# Audio_panel_Embedded_Mega_breakout.net
KiCad netlist of a schematic drawn in EAGLE
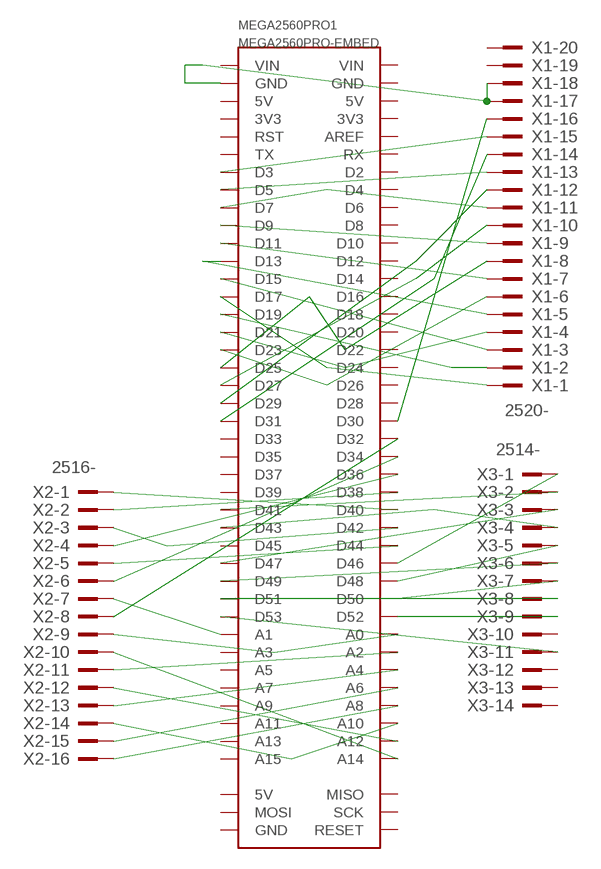
[diagram p0: schematic, sheet 1]

(export (version "E")
  (design (tool "Eeschema 10.0.6"))
  (components
    (comp (ref "MEGA2560PRO1")
      (value "MEGA2560PRO-EMBED")
      (footprint "eagle-import:MEGA2560PRO-EMBED")
      (libsource (lib "eagle-import") (part "MEGA2560PRO-EMBED"))
    )
    (comp (ref "X1")
      (value "2520-")
      (footprint "eagle-import:PAK100_2500-20")
      (libsource (lib "eagle-import") (part "2520-"))
    )
    (comp (ref "X2")
      (value "2516-")
      (footprint "eagle-import:PAK100_2500-16")
      (libsource (lib "eagle-import") (part "2516-"))
    )
    (comp (ref "X3")
      (value "2514-")
      (footprint "eagle-import:PAK100_2500-14")
      (libsource (lib "eagle-import") (part "2514-"))
    )
  )
  (nets
    (net (code "1") (name "Net-(X1A-KL)") (class "Default")
      (node (ref "MEGA2560PRO1") (pin "D17") (pinfunction "D17_D17") (pintype "bidirectional"))
      (node (ref "X1") (pin "1") (pinfunction "KL_1") (pintype "passive"))
    )
    (net (code "2") (name "Net-(X1B-KL)") (class "Default")
      (node (ref "MEGA2560PRO1") (pin "D27") (pinfunction "D27_D27") (pintype "bidirectional"))
      (node (ref "X1") (pin "10") (pinfunction "KL_10") (pintype "passive"))
    )
    (net (code "3") (name "Net-(X1C-KL)") (class "Default")
      (node (ref "MEGA2560PRO1") (pin "D7") (pinfunction "D7_D7") (pintype "bidirectional"))
      (node (ref "X1") (pin "11") (pinfunction "KL_11") (pintype "passive"))
    )
    (net (code "4") (name "Net-(X1D-KL)") (class "Default")
      (node (ref "MEGA2560PRO1") (pin "D29") (pinfunction "D29_D29") (pintype "bidirectional"))
      (node (ref "X1") (pin "12") (pinfunction "KL_12") (pintype "passive"))
    )
    (net (code "5") (name "Net-(X1E-KL)") (class "Default")
      (node (ref "MEGA2560PRO1") (pin "D5") (pinfunction "D5_D5") (pintype "bidirectional"))
      (node (ref "X1") (pin "13") (pinfunction "KL_13") (pintype "passive"))
    )
    (net (code "6") (name "Net-(X1F-KL)") (class "Default")
      (node (ref "MEGA2560PRO1") (pin "D31") (pinfunction "D31_D31") (pintype "bidirectional"))
      (node (ref "X1") (pin "14") (pinfunction "KL_14") (pintype "passive"))
    )
    (net (code "7") (name "Net-(X1G-KL)") (class "Default")
      (node (ref "MEGA2560PRO1") (pin "D3") (pinfunction "D3_D3") (pintype "bidirectional"))
      (node (ref "X1") (pin "15") (pinfunction "KL_15") (pintype "passive"))
    )
    (net (code "8") (name "Net-(X1H-KL)") (class "Default")
      (node (ref "MEGA2560PRO1") (pin "D30") (pinfunction "D30_D30") (pintype "bidirectional"))
      (node (ref "X1") (pin "16") (pinfunction "KL_16") (pintype "passive"))
    )
    (net (code "9") (name "Net-(X1I-KL)") (class "Default")
      (node (ref "MEGA2560PRO1") (pin "GND@1") (pinfunction "GND_GND@1") (pintype "bidirectional"))
      (node (ref "X1") (pin "17") (pinfunction "KL_17") (pintype "passive"))
      (node (ref "X1") (pin "18") (pinfunction "KL_18") (pintype "passive"))
    )
    (net (code "10") (name "Net-(X1L-KL)") (class "Default")
      (node (ref "MEGA2560PRO1") (pin "D19") (pinfunction "D19_D19") (pintype "bidirectional"))
      (node (ref "X1") (pin "2") (pinfunction "KL_2") (pintype "passive"))
    )
    (net (code "11") (name "Net-(X1N-KL)") (class "Default")
      (node (ref "MEGA2560PRO1") (pin "D15") (pinfunction "D15_D15") (pintype "bidirectional"))
      (node (ref "X1") (pin "3") (pinfunction "KL_3") (pintype "passive"))
    )
    (net (code "12") (name "Net-(X1O-KL)") (class "Default")
      (node (ref "MEGA2560PRO1") (pin "D21") (pinfunction "D21_D21") (pintype "bidirectional"))
      (node (ref "X1") (pin "4") (pinfunction "KL_4") (pintype "passive"))
    )
    (net (code "13") (name "Net-(X1P-KL)") (class "Default")
      (node (ref "MEGA2560PRO1") (pin "D13") (pinfunction "D13_D13") (pintype "bidirectional"))
      (node (ref "X1") (pin "5") (pinfunction "KL_5") (pintype "passive"))
    )
    (net (code "14") (name "Net-(X1Q-KL)") (class "Default")
      (node (ref "MEGA2560PRO1") (pin "D23") (pinfunction "D23_D23") (pintype "bidirectional"))
      (node (ref "X1") (pin "6") (pinfunction "KL_6") (pintype "passive"))
    )
    (net (code "15") (name "Net-(X1R-KL)") (class "Default")
      (node (ref "MEGA2560PRO1") (pin "D11") (pinfunction "D11_D11") (pintype "bidirectional"))
      (node (ref "X1") (pin "7") (pinfunction "KL_7") (pintype "passive"))
    )
    (net (code "16") (name "Net-(X1S-KL)") (class "Default")
      (node (ref "MEGA2560PRO1") (pin "D25") (pinfunction "D25_D25") (pintype "bidirectional"))
      (node (ref "X1") (pin "8") (pinfunction "KL_8") (pintype "passive"))
    )
    (net (code "17") (name "Net-(X1T-KL)") (class "Default")
      (node (ref "MEGA2560PRO1") (pin "D9") (pinfunction "D9_D9") (pintype "bidirectional"))
      (node (ref "X1") (pin "9") (pinfunction "KL_9") (pintype "passive"))
    )
    (net (code "18") (name "Net-(X2A-KL)") (class "Default")
      (node (ref "MEGA2560PRO1") (pin "D40") (pinfunction "D40_D40") (pintype "bidirectional"))
      (node (ref "X2") (pin "1") (pinfunction "KL_1") (pintype "passive"))
    )
    (net (code "19") (name "Net-(X2B-KL)") (class "Default")
      (node (ref "MEGA2560PRO1") (pin "A14") (pinfunction "A14_A14") (pintype "bidirectional"))
      (node (ref "X2") (pin "10") (pinfunction "KL_10") (pintype "passive"))
    )
    (net (code "20") (name "Net-(X2C-KL)") (class "Default")
      (node (ref "MEGA2560PRO1") (pin "A2") (pinfunction "A2_A2") (pintype "bidirectional"))
      (node (ref "X2") (pin "11") (pinfunction "KL_11") (pintype "passive"))
    )
    (net (code "21") (name "Net-(X2D-KL)") (class "Default")
      (node (ref "MEGA2560PRO1") (pin "A12") (pinfunction "A12_A12") (pintype "bidirectional"))
      (node (ref "X2") (pin "12") (pinfunction "KL_12") (pintype "passive"))
    )
    (net (code "22") (name "Net-(X2E-KL)") (class "Default")
      (node (ref "MEGA2560PRO1") (pin "A4") (pinfunction "A4_A4") (pintype "bidirectional"))
      (node (ref "X2") (pin "13") (pinfunction "KL_13") (pintype "passive"))
    )
    (net (code "23") (name "Net-(X2F-KL)") (class "Default")
      (node (ref "MEGA2560PRO1") (pin "A10") (pinfunction "A10_A10") (pintype "bidirectional"))
      (node (ref "X2") (pin "14") (pinfunction "KL_14") (pintype "passive"))
    )
    (net (code "24") (name "Net-(X2G-KL)") (class "Default")
      (node (ref "MEGA2560PRO1") (pin "A6") (pinfunction "A6_A6") (pintype "bidirectional"))
      (node (ref "X2") (pin "15") (pinfunction "KL_15") (pintype "passive"))
    )
    (net (code "25") (name "Net-(X2H-KL)") (class "Default")
      (node (ref "MEGA2560PRO1") (pin "A8") (pinfunction "A8_A8") (pintype "bidirectional"))
      (node (ref "X2") (pin "16") (pinfunction "KL_16") (pintype "passive"))
    )
    (net (code "26") (name "Net-(X2I-KL)") (class "Default")
      (node (ref "MEGA2560PRO1") (pin "D38") (pinfunction "D38_D38") (pintype "bidirectional"))
      (node (ref "X2") (pin "2") (pinfunction "KL_2") (pintype "passive"))
    )
    (net (code "27") (name "Net-(X2J-KL)") (class "Default")
      (node (ref "MEGA2560PRO1") (pin "D42") (pinfunction "D42_D42") (pintype "bidirectional"))
      (node (ref "X2") (pin "3") (pinfunction "KL_3") (pintype "passive"))
    )
    (net (code "28") (name "Net-(X2K-KL)") (class "Default")
      (node (ref "MEGA2560PRO1") (pin "D36") (pinfunction "D36_D36") (pintype "bidirectional"))
      (node (ref "X2") (pin "4") (pinfunction "KL_4") (pintype "passive"))
    )
    (net (code "29") (name "Net-(X2L-KL)") (class "Default")
      (node (ref "MEGA2560PRO1") (pin "D44") (pinfunction "D44_D44") (pintype "bidirectional"))
      (node (ref "X2") (pin "5") (pinfunction "KL_5") (pintype "passive"))
    )
    (net (code "30") (name "Net-(X2M-KL)") (class "Default")
      (node (ref "MEGA2560PRO1") (pin "D34") (pinfunction "D34_D34") (pintype "bidirectional"))
      (node (ref "X2") (pin "6") (pinfunction "KL_6") (pintype "passive"))
    )
    (net (code "31") (name "Net-(X2N-KL)") (class "Default")
      (node (ref "MEGA2560PRO1") (pin "A1") (pinfunction "A1_A1") (pintype "bidirectional"))
      (node (ref "X2") (pin "7") (pinfunction "KL_7") (pintype "passive"))
    )
    (net (code "32") (name "Net-(X2O-KL)") (class "Default")
      (node (ref "MEGA2560PRO1") (pin "D32") (pinfunction "D32_D32") (pintype "bidirectional"))
      (node (ref "X2") (pin "8") (pinfunction "KL_8") (pintype "passive"))
    )
    (net (code "33") (name "Net-(X2P-KL)") (class "Default")
      (node (ref "MEGA2560PRO1") (pin "A0") (pinfunction "A0_A0") (pintype "bidirectional"))
      (node (ref "X2") (pin "9") (pinfunction "KL_9") (pintype "passive"))
    )
    (net (code "34") (name "Net-(X3A-KL)") (class "Default")
      (node (ref "MEGA2560PRO1") (pin "D46") (pinfunction "D46_D46") (pintype "bidirectional"))
      (node (ref "X3") (pin "1") (pinfunction "KL_1") (pintype "passive"))
    )
    (net (code "35") (name "Net-(X3C-KL)") (class "Default")
      (node (ref "MEGA2560PRO1") (pin "D53") (pinfunction "D53_D53") (pintype "bidirectional"))
      (node (ref "X3") (pin "11") (pinfunction "KL_11") (pintype "passive"))
    )
    (net (code "36") (name "Net-(X3G-KL)") (class "Default")
      (node (ref "MEGA2560PRO1") (pin "D41") (pinfunction "D41_D41") (pintype "bidirectional"))
      (node (ref "X3") (pin "2") (pinfunction "KL_2") (pintype "passive"))
    )
    (net (code "37") (name "Net-(X3H-KL)") (class "Default")
      (node (ref "MEGA2560PRO1") (pin "D47") (pinfunction "D47_D47") (pintype "bidirectional"))
      (node (ref "X3") (pin "3") (pinfunction "KL_3") (pintype "passive"))
    )
    (net (code "38") (name "Net-(X3I-KL)") (class "Default")
      (node (ref "MEGA2560PRO1") (pin "D43") (pinfunction "D43_D43") (pintype "bidirectional"))
      (node (ref "X3") (pin "4") (pinfunction "KL_4") (pintype "passive"))
    )
    (net (code "39") (name "Net-(X3J-KL)") (class "Default")
      (node (ref "MEGA2560PRO1") (pin "D48") (pinfunction "D48_D48") (pintype "bidirectional"))
      (node (ref "X3") (pin "5") (pinfunction "KL_5") (pintype "passive"))
    )
    (net (code "40") (name "Net-(X3K-KL)") (class "Default")
      (node (ref "MEGA2560PRO1") (pin "D49") (pinfunction "D49_D49") (pintype "bidirectional"))
      (node (ref "X3") (pin "6") (pinfunction "KL_6") (pintype "passive"))
    )
    (net (code "41") (name "Net-(X3L-KL)") (class "Default")
      (node (ref "MEGA2560PRO1") (pin "D50") (pinfunction "D50_D50") (pintype "bidirectional"))
      (node (ref "X3") (pin "7") (pinfunction "KL_7") (pintype "passive"))
    )
    (net (code "42") (name "Net-(X3M-KL)") (class "Default")
      (node (ref "MEGA2560PRO1") (pin "D51") (pinfunction "D51_D51") (pintype "bidirectional"))
      (node (ref "X3") (pin "8") (pinfunction "KL_8") (pintype "passive"))
    )
    (net (code "43") (name "Net-(X3N-KL)") (class "Default")
      (node (ref "MEGA2560PRO1") (pin "D52") (pinfunction "D52_D52") (pintype "bidirectional"))
      (node (ref "X3") (pin "9") (pinfunction "KL_9") (pintype "passive"))
    )
    (net (code "44") (name "unconnected-(MEGA2560PRO1-3V3-Pad3V3@1)") (class "Default")
      (node (ref "MEGA2560PRO1") (pin "3V3@1") (pinfunction "3V3_3V3@1") (pintype "bidirectional"))
    )
    (net (code "45") (name "unconnected-(MEGA2560PRO1-3V3-Pad3V3@2)") (class "Default")
      (node (ref "MEGA2560PRO1") (pin "3V3@2") (pinfunction "3V3_3V3@2") (pintype "bidirectional"))
    )
    (net (code "46") (name "unconnected-(MEGA2560PRO1-5V-Pad5V@1)") (class "Default")
      (node (ref "MEGA2560PRO1") (pin "5V@1") (pinfunction "5V_5V@1") (pintype "bidirectional"))
    )
    (net (code "47") (name "unconnected-(MEGA2560PRO1-5V-Pad5V@2)") (class "Default")
      (node (ref "MEGA2560PRO1") (pin "5V@2") (pinfunction "5V_5V@2") (pintype "bidirectional"))
    )
    (net (code "48") (name "unconnected-(MEGA2560PRO1-5V-Pad5V@3)") (class "Default")
      (node (ref "MEGA2560PRO1") (pin "5V@3") (pinfunction "5V_5V@3") (pintype "bidirectional"))
    )
    (net (code "49") (name "unconnected-(MEGA2560PRO1-GND-PadGND@2)") (class "Default")
      (node (ref "MEGA2560PRO1") (pin "GND@2") (pinfunction "GND_GND@2") (pintype "bidirectional"))
    )
    (net (code "50") (name "unconnected-(MEGA2560PRO1-GND-PadGND@3)") (class "Default")
      (node (ref "MEGA2560PRO1") (pin "GND@3") (pinfunction "GND_GND@3") (pintype "bidirectional"))
    )
    (net (code "51") (name "unconnected-(MEGA2560PRO1-PadA3)") (class "Default")
      (node (ref "MEGA2560PRO1") (pin "A3") (pinfunction "A3_A3") (pintype "bidirectional"))
    )
    (net (code "52") (name "unconnected-(MEGA2560PRO1-PadA5)") (class "Default")
      (node (ref "MEGA2560PRO1") (pin "A5") (pinfunction "A5_A5") (pintype "bidirectional"))
    )
    (net (code "53") (name "unconnected-(MEGA2560PRO1-PadA7)") (class "Default")
      (node (ref "MEGA2560PRO1") (pin "A7") (pinfunction "A7_A7") (pintype "bidirectional"))
    )
    (net (code "54") (name "unconnected-(MEGA2560PRO1-PadA9)") (class "Default")
      (node (ref "MEGA2560PRO1") (pin "A9") (pinfunction "A9_A9") (pintype "bidirectional"))
    )
    (net (code "55") (name "unconnected-(MEGA2560PRO1-PadA11)") (class "Default")
      (node (ref "MEGA2560PRO1") (pin "A11") (pinfunction "A11_A11") (pintype "bidirectional"))
    )
    (net (code "56") (name "unconnected-(MEGA2560PRO1-PadA13)") (class "Default")
      (node (ref "MEGA2560PRO1") (pin "A13") (pinfunction "A13_A13") (pintype "bidirectional"))
    )
    (net (code "57") (name "unconnected-(MEGA2560PRO1-PadA15)") (class "Default")
      (node (ref "MEGA2560PRO1") (pin "A15") (pinfunction "A15_A15") (pintype "bidirectional"))
    )
    (net (code "58") (name "unconnected-(MEGA2560PRO1-PadAREF)") (class "Default")
      (node (ref "MEGA2560PRO1") (pin "AREF") (pinfunction "AREF_AREF") (pintype "bidirectional"))
    )
    (net (code "59") (name "unconnected-(MEGA2560PRO1-PadD2)") (class "Default")
      (node (ref "MEGA2560PRO1") (pin "D2") (pinfunction "D2_D2") (pintype "bidirectional"))
    )
    (net (code "60") (name "unconnected-(MEGA2560PRO1-PadD4)") (class "Default")
      (node (ref "MEGA2560PRO1") (pin "D4") (pinfunction "D4_D4") (pintype "bidirectional"))
    )
    (net (code "61") (name "unconnected-(MEGA2560PRO1-PadD6)") (class "Default")
      (node (ref "MEGA2560PRO1") (pin "D6") (pinfunction "D6_D6") (pintype "bidirectional"))
    )
    (net (code "62") (name "unconnected-(MEGA2560PRO1-PadD8)") (class "Default")
      (node (ref "MEGA2560PRO1") (pin "D8") (pinfunction "D8_D8") (pintype "bidirectional"))
    )
    (net (code "63") (name "unconnected-(MEGA2560PRO1-PadD10)") (class "Default")
      (node (ref "MEGA2560PRO1") (pin "D10") (pinfunction "D10_D10") (pintype "bidirectional"))
    )
    (net (code "64") (name "unconnected-(MEGA2560PRO1-PadD12)") (class "Default")
      (node (ref "MEGA2560PRO1") (pin "D12") (pinfunction "D12_D12") (pintype "bidirectional"))
    )
    (net (code "65") (name "unconnected-(MEGA2560PRO1-PadD14)") (class "Default")
      (node (ref "MEGA2560PRO1") (pin "D14") (pinfunction "D14_D14") (pintype "bidirectional"))
    )
    (net (code "66") (name "unconnected-(MEGA2560PRO1-PadD16)") (class "Default")
      (node (ref "MEGA2560PRO1") (pin "D16") (pinfunction "D16_D16") (pintype "bidirectional"))
    )
    (net (code "67") (name "unconnected-(MEGA2560PRO1-PadD18)") (class "Default")
      (node (ref "MEGA2560PRO1") (pin "D18") (pinfunction "D18_D18") (pintype "bidirectional"))
    )
    (net (code "68") (name "unconnected-(MEGA2560PRO1-PadD20)") (class "Default")
      (node (ref "MEGA2560PRO1") (pin "D20") (pinfunction "D20_D20") (pintype "bidirectional"))
    )
    (net (code "69") (name "unconnected-(MEGA2560PRO1-PadD22)") (class "Default")
      (node (ref "MEGA2560PRO1") (pin "D22") (pinfunction "D22_D22") (pintype "bidirectional"))
    )
    (net (code "70") (name "unconnected-(MEGA2560PRO1-PadD24)") (class "Default")
      (node (ref "MEGA2560PRO1") (pin "D24") (pinfunction "D24_D24") (pintype "bidirectional"))
    )
    (net (code "71") (name "unconnected-(MEGA2560PRO1-PadD26)") (class "Default")
      (node (ref "MEGA2560PRO1") (pin "D26") (pinfunction "D26_D26") (pintype "bidirectional"))
    )
    (net (code "72") (name "unconnected-(MEGA2560PRO1-PadD28)") (class "Default")
      (node (ref "MEGA2560PRO1") (pin "D28") (pinfunction "D28_D28") (pintype "bidirectional"))
    )
    (net (code "73") (name "unconnected-(MEGA2560PRO1-PadD33)") (class "Default")
      (node (ref "MEGA2560PRO1") (pin "D33") (pinfunction "D33_D33") (pintype "bidirectional"))
    )
    (net (code "74") (name "unconnected-(MEGA2560PRO1-PadD35)") (class "Default")
      (node (ref "MEGA2560PRO1") (pin "D35") (pinfunction "D35_D35") (pintype "bidirectional"))
    )
    (net (code "75") (name "unconnected-(MEGA2560PRO1-PadD37)") (class "Default")
      (node (ref "MEGA2560PRO1") (pin "D37") (pinfunction "D37_D37") (pintype "bidirectional"))
    )
    (net (code "76") (name "unconnected-(MEGA2560PRO1-PadD39)") (class "Default")
      (node (ref "MEGA2560PRO1") (pin "D39") (pinfunction "D39_D39") (pintype "bidirectional"))
    )
    (net (code "77") (name "unconnected-(MEGA2560PRO1-PadD45)") (class "Default")
      (node (ref "MEGA2560PRO1") (pin "D45") (pinfunction "D45_D45") (pintype "bidirectional"))
    )
    (net (code "78") (name "unconnected-(MEGA2560PRO1-PadMISO)") (class "Default")
      (node (ref "MEGA2560PRO1") (pin "MISO") (pinfunction "MISO_MISO") (pintype "bidirectional"))
    )
    (net (code "79") (name "unconnected-(MEGA2560PRO1-PadMOSI)") (class "Default")
      (node (ref "MEGA2560PRO1") (pin "MOSI") (pinfunction "MOSI_MOSI") (pintype "bidirectional"))
    )
    (net (code "80") (name "unconnected-(MEGA2560PRO1-PadRESET)") (class "Default")
      (node (ref "MEGA2560PRO1") (pin "RESET") (pinfunction "RESET_RESET") (pintype "bidirectional"))
    )
    (net (code "81") (name "unconnected-(MEGA2560PRO1-PadRST)") (class "Default")
      (node (ref "MEGA2560PRO1") (pin "RST") (pinfunction "RST_RST") (pintype "bidirectional"))
    )
    (net (code "82") (name "unconnected-(MEGA2560PRO1-PadRX)") (class "Default")
      (node (ref "MEGA2560PRO1") (pin "RX") (pinfunction "RX_RX") (pintype "bidirectional"))
    )
    (net (code "83") (name "unconnected-(MEGA2560PRO1-PadSCK)") (class "Default")
      (node (ref "MEGA2560PRO1") (pin "SCK") (pinfunction "SCK_SCK") (pintype "bidirectional"))
    )
    (net (code "84") (name "unconnected-(MEGA2560PRO1-PadTX)") (class "Default")
      (node (ref "MEGA2560PRO1") (pin "TX") (pinfunction "TX_TX") (pintype "bidirectional"))
    )
    (net (code "85") (name "unconnected-(MEGA2560PRO1-VIN-PadVIN@1)") (class "Default")
      (node (ref "MEGA2560PRO1") (pin "VIN@1") (pinfunction "VIN_VIN@1") (pintype "bidirectional"))
    )
    (net (code "86") (name "unconnected-(MEGA2560PRO1-VIN-PadVIN@2)") (class "Default")
      (node (ref "MEGA2560PRO1") (pin "VIN@2") (pinfunction "VIN_VIN@2") (pintype "bidirectional"))
    )
    (net (code "87") (name "unconnected-(X1K-KL-Pad19)") (class "Default")
      (node (ref "X1") (pin "19") (pinfunction "KL_19") (pintype "passive"))
    )
    (net (code "88") (name "unconnected-(X1M-KL-Pad20)") (class "Default")
      (node (ref "X1") (pin "20") (pinfunction "KL_20") (pintype "passive"))
    )
    (net (code "89") (name "unconnected-(X3B-KL-Pad10)") (class "Default")
      (node (ref "X3") (pin "10") (pinfunction "KL_10") (pintype "passive"))
    )
    (net (code "90") (name "unconnected-(X3D-KL-Pad12)") (class "Default")
      (node (ref "X3") (pin "12") (pinfunction "KL_12") (pintype "passive"))
    )
    (net (code "91") (name "unconnected-(X3E-KL-Pad13)") (class "Default")
      (node (ref "X3") (pin "13") (pinfunction "KL_13") (pintype "passive"))
    )
    (net (code "92") (name "unconnected-(X3F-KL-Pad14)") (class "Default")
      (node (ref "X3") (pin "14") (pinfunction "KL_14") (pintype "passive"))
    )
  )
)
